# HCM_wiring_diagram.net
KiCad netlist of a schematic drawn in Altium Designer
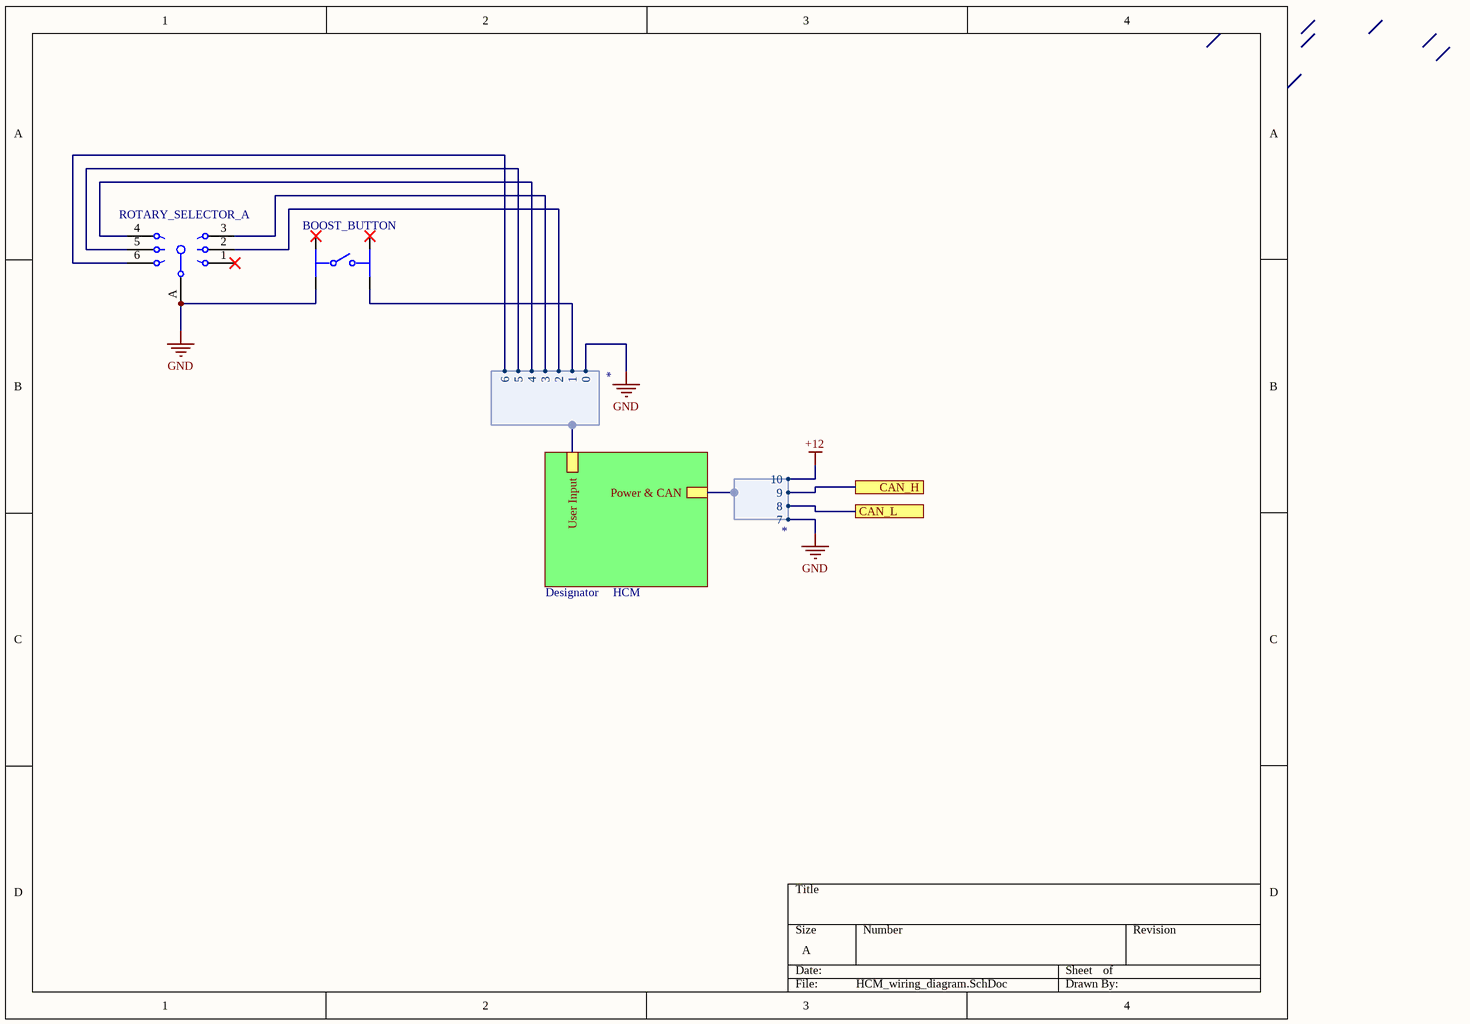
[diagram p0: HCM_wiring_diagram.SchDoc]

(export (version "E")
  (design (tool "Eeschema 10.0.6"))
  (components
    (comp (ref "BOOST_BUTTON")
      (value "ESE-20C441")
      (footprint "FP-ESE-20C441-MFG")
      (description "SWITCH PUSH SPST-NO 0.1A 14V")
      (libsource (lib "Altium Content Vault") (part "7af1e63d87958053304b0ff27c3d6bc"))
    )
    (comp (ref "ROTARY_SELECTOR_")
      (value "A20615RNCQK")
      (footprint "CKCP-A20615RNCQ-14_V")
      (description "A Series Rotary Switch, 2 Poles, 6 Positions, 30 deg Angle of Throw, -30 to 85 degC, RoHS")
      (fields (field (name "MANUFACTURER") "C&K Components"))
      (libsource (lib "Altium Content Vault") (part "CKCP-SW_DP6T-14"))
    )
  )
  (nets
    (net (code "2") (name "/1") (class "Default")
      (node (ref "BOOST_BUTTON") (pin "D") (pinfunction "D_D") (pintype "passive"))
    )
    (net (code "3") (name "/2") (class "Default")
      (node (ref "ROTARY_SELECTOR_") (pin "2") (pinfunction "2_2") (pintype "passive"))
    )
    (net (code "4") (name "/3") (class "Default")
      (node (ref "ROTARY_SELECTOR_") (pin "3") (pinfunction "3_3") (pintype "passive"))
    )
    (net (code "5") (name "/4") (class "Default")
      (node (ref "ROTARY_SELECTOR_") (pin "4") (pinfunction "4_4") (pintype "passive"))
    )
    (net (code "6") (name "/5") (class "Default")
      (node (ref "ROTARY_SELECTOR_") (pin "5") (pinfunction "5_5") (pintype "passive"))
    )
    (net (code "7") (name "/6") (class "Default")
      (node (ref "ROTARY_SELECTOR_") (pin "6") (pinfunction "6_6") (pintype "passive"))
    )
    (net (code "12") (name "GND") (class "Default")
      (node (ref "BOOST_BUTTON") (pin "C") (pinfunction "C_C") (pintype "passive"))
      (node (ref "ROTARY_SELECTOR_") (pin "A") (pinfunction "A_A") (pintype "passive"))
    )
    (net (code "13") (name "unconnected-(BOOST_BUTTON-PadA)") (class "Default")
      (node (ref "BOOST_BUTTON") (pin "A") (pinfunction "A_A") (pintype "passive+no_connect"))
    )
    (net (code "14") (name "unconnected-(BOOST_BUTTON-PadB)") (class "Default")
      (node (ref "BOOST_BUTTON") (pin "B") (pinfunction "B_B") (pintype "passive+no_connect"))
    )
    (net (code "15") (name "unconnected-(ROTARY_SELECTOR_-Pad1)") (class "Default")
      (node (ref "ROTARY_SELECTOR_") (pin "1") (pinfunction "1_1") (pintype "passive+no_connect"))
    )
  )
)
